# soic8-longpad.net
KiCad netlist of a schematic drawn in EAGLE
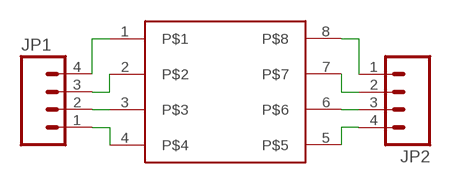
[diagram p0: schematic, sheet 1]

(export (version "E")
  (design (tool "Eeschema 10.0.6"))
  (components
    (comp (ref "JP1")
      (value "M04NO_SILK_ALL_ROUND")
      (footprint "eagle-import:1X04_NO_SILK_ALL_ROUND")
      (libsource (lib "eagle-import") (part "M04NO_SILK_ALL_ROUND"))
    )
    (comp (ref "JP2")
      (value "M04NO_SILK_ALL_ROUND")
      (footprint "eagle-import:1X04_NO_SILK_ALL_ROUND")
      (libsource (lib "eagle-import") (part "M04NO_SILK_ALL_ROUND"))
    )
    (comp (ref "U$1")
      (value "SOIC8")
      (footprint "eagle-import:SOIC8-LONGPAD")
      (libsource (lib "eagle-import") (part "SOIC8-LONGPAD"))
    )
  )
  (nets
    (net (code "1") (name "Net-(U$1-P$1)") (class "Default")
      (node (ref "JP1") (pin "4") (pinfunction "4_4") (pintype "passive"))
      (node (ref "U$1") (pin "1") (pinfunction "P$1_1") (pintype "bidirectional"))
    )
    (net (code "2") (name "Net-(U$1-P$2)") (class "Default")
      (node (ref "JP1") (pin "3") (pinfunction "3_3") (pintype "passive"))
      (node (ref "U$1") (pin "2") (pinfunction "P$2_2") (pintype "bidirectional"))
    )
    (net (code "3") (name "Net-(U$1-P$3)") (class "Default")
      (node (ref "JP1") (pin "2") (pinfunction "2_2") (pintype "passive"))
      (node (ref "U$1") (pin "3") (pinfunction "P$3_3") (pintype "bidirectional"))
    )
    (net (code "4") (name "Net-(U$1-P$4)") (class "Default")
      (node (ref "JP1") (pin "1") (pinfunction "1_1") (pintype "passive"))
      (node (ref "U$1") (pin "4") (pinfunction "P$4_4") (pintype "bidirectional"))
    )
    (net (code "5") (name "Net-(U$1-P$5)") (class "Default")
      (node (ref "JP2") (pin "4") (pinfunction "4_4") (pintype "passive"))
      (node (ref "U$1") (pin "5") (pinfunction "P$5_5") (pintype "bidirectional"))
    )
    (net (code "6") (name "Net-(U$1-P$6)") (class "Default")
      (node (ref "JP2") (pin "3") (pinfunction "3_3") (pintype "passive"))
      (node (ref "U$1") (pin "6") (pinfunction "P$6_6") (pintype "bidirectional"))
    )
    (net (code "7") (name "Net-(U$1-P$7)") (class "Default")
      (node (ref "JP2") (pin "2") (pinfunction "2_2") (pintype "passive"))
      (node (ref "U$1") (pin "7") (pinfunction "P$7_7") (pintype "bidirectional"))
    )
    (net (code "8") (name "Net-(U$1-P$8)") (class "Default")
      (node (ref "JP2") (pin "1") (pinfunction "1_1") (pintype "passive"))
      (node (ref "U$1") (pin "8") (pinfunction "P$8_8") (pintype "bidirectional"))
    )
  )
)
